# ProPrj_M0G3507__2025-04-02_2025-7-14_232.net
KiCad netlist of a schematic drawn in EasyEDA Pro
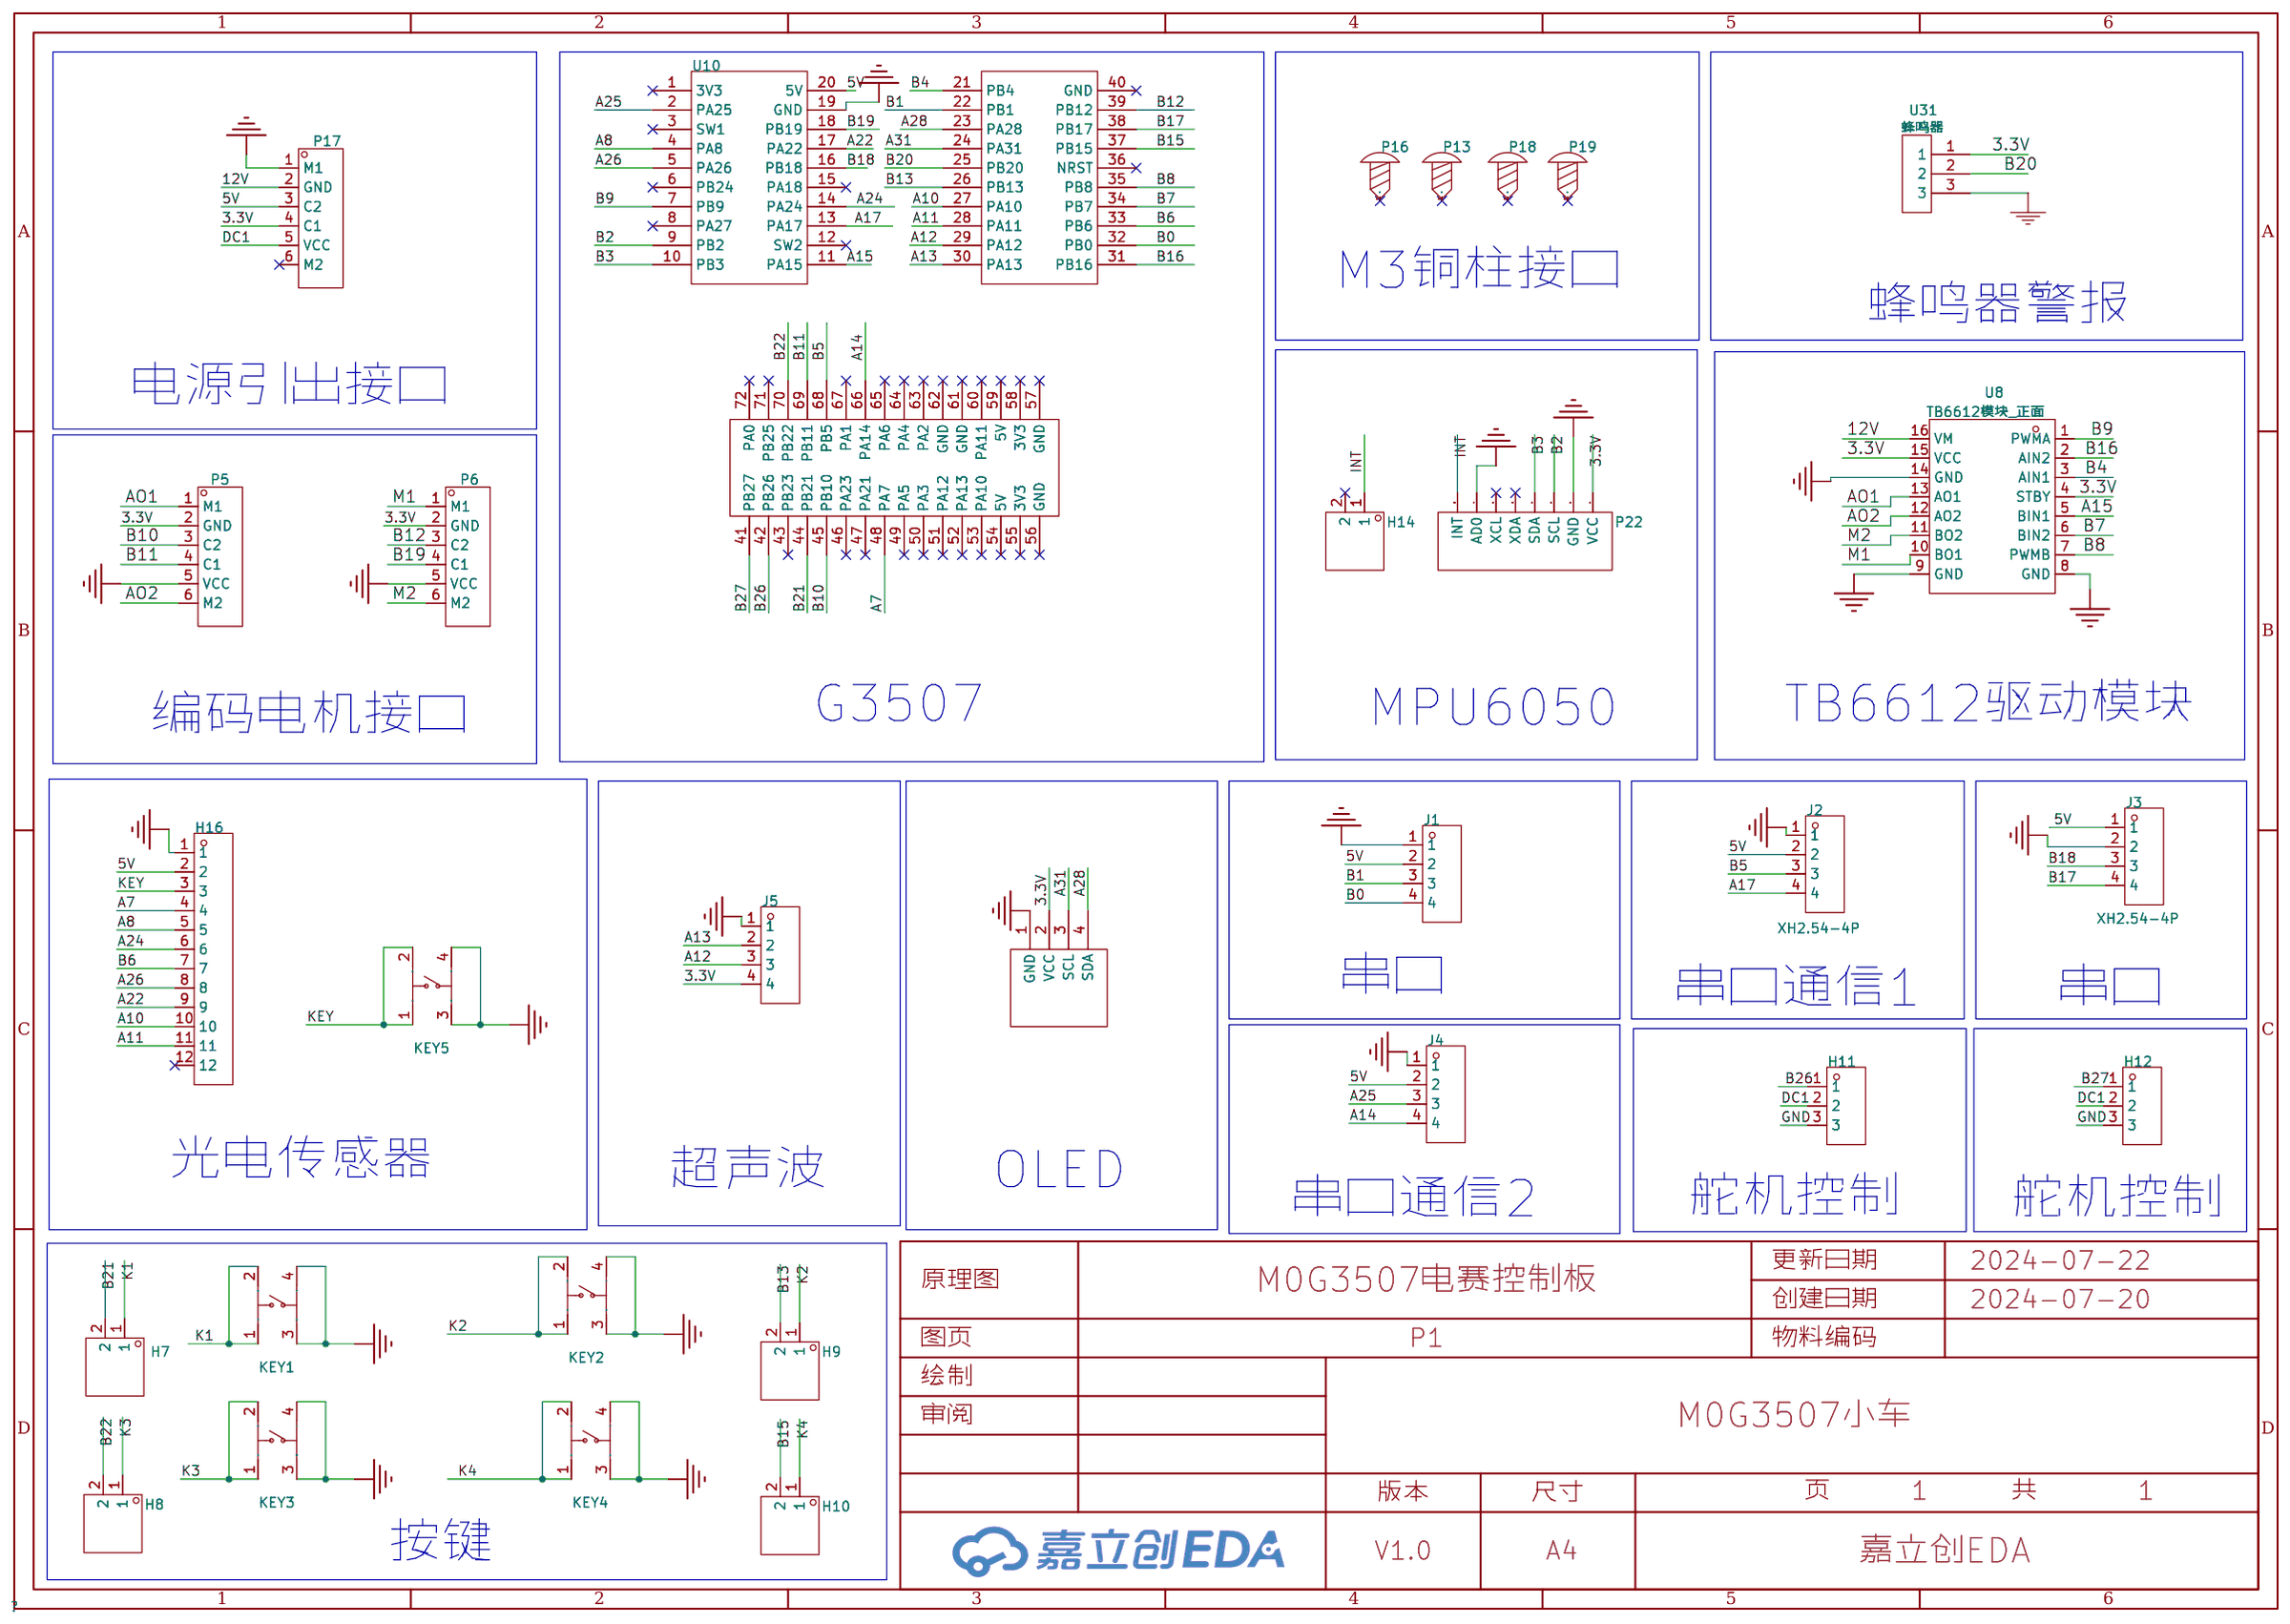
[diagram p0: schematic sheet]

(export (version "E")
  (design (tool "Eeschema 10.0.6"))
  (components
    (comp (ref "H7")
      (value "~")
      (footprint "easyedapro:HDR-TH_2P-P2.54-V-M-1")
      (fields (field (name "Manufacturer Part") "B-2100S02P-A110") (field (name "Manufacturer") "Ckmtw(灿科盟)"))
      (libsource (lib "easyedapro") (part "210S-1*2P L=11.6MMGold-plated black"))
    )
    (comp (ref "H8")
      (value "~")
      (footprint "easyedapro:HDR-TH_2P-P2.54-V-M-1")
      (fields (field (name "Manufacturer Part") "B-2100S02P-A110") (field (name "Manufacturer") "Ckmtw(灿科盟)"))
      (libsource (lib "easyedapro") (part "210S-1*2P L=11.6MMGold-plated black"))
    )
    (comp (ref "H9")
      (value "~")
      (footprint "easyedapro:HDR-TH_2P-P2.54-V-M-1")
      (fields (field (name "Manufacturer Part") "B-2100S02P-A110") (field (name "Manufacturer") "Ckmtw(灿科盟)"))
      (libsource (lib "easyedapro") (part "210S-1*2P L=11.6MMGold-plated black"))
    )
    (comp (ref "H10")
      (value "~")
      (footprint "easyedapro:HDR-TH_2P-P2.54-V-M-1")
      (fields (field (name "Manufacturer Part") "B-2100S02P-A110") (field (name "Manufacturer") "Ckmtw(灿科盟)"))
      (libsource (lib "easyedapro") (part "210S-1*2P L=11.6MMGold-plated black"))
    )
    (comp (ref "H11")
      (value "2.54-1*3P正弯针")
      (footprint "easyedapro:3P排针座")
      (fields (field (name "Manufacturer") "BOOMELE(博穆精密)"))
      (libsource (lib "easyedapro") (part "2.54-1*3P排针座"))
    )
    (comp (ref "H12")
      (value "2.54-1*3P正弯针")
      (footprint "easyedapro:3P排针座")
      (fields (field (name "Manufacturer") "BOOMELE(博穆精密)"))
      (libsource (lib "easyedapro") (part "2.54-1*3P排针座"))
    )
    (comp (ref "H14")
      (value "~")
      (footprint "easyedapro:HDR-TH_2P-P2.54-V-M-1")
      (fields (field (name "Manufacturer Part") "B-2100S02P-A110") (field (name "Manufacturer") "Ckmtw(灿科盟)"))
      (libsource (lib "easyedapro") (part "210S-1*2P L=11.6MMGold-plated black"))
    )
    (comp (ref "H16")
      (value "PZ254V-11-12P")
      (footprint "easyedapro:HDR-TH_12P-P2.54-V-M")
      (fields (field (name "Manufacturer") "XFCN(兴飞)"))
      (libsource (lib "easyedapro") (part "PZ254V-11-12P"))
    )
    (comp (ref "J1")
      (value "XH2.54-4P")
      (footprint "easyedapro:CONN-TH_4P-P2.50-XH2.54-4P")
      (libsource (lib "easyedapro") (part "XH2.54-4P"))
    )
    (comp (ref "J2")
      (value "XH2.54-4P")
      (footprint "easyedapro:CONN-TH_4P-P2.50-XH2.54-4P")
      (libsource (lib "easyedapro") (part "XH2.54-4P"))
    )
    (comp (ref "J3")
      (value "XH2.54-4P")
      (footprint "easyedapro:CONN-TH_4P-P2.50-XH2.54-4P")
      (libsource (lib "easyedapro") (part "XH2.54-4P"))
    )
    (comp (ref "J4")
      (value "XH2.54-4P")
      (footprint "easyedapro:CONN-TH_4P-P2.50-XH2.54-4P")
      (libsource (lib "easyedapro") (part "XH2.54-4P"))
    )
    (comp (ref "J5")
      (value "XH2.54-4P")
      (footprint "easyedapro:CONN-TH_4P-P2.50-XH2.54-4P")
      (libsource (lib "easyedapro") (part "XH2.54-4P"))
    )
    (comp (ref "KEY1")
      (value "TC-6610-9-260G")
      (footprint "easyedapro:SW-TH_4P-L5.0-W5.0-P4.50-LS6.5")
      (fields (field (name "Manufacturer") "HCTL(华灿天禄)"))
      (libsource (lib "easyedapro") (part "TC-6610-9-260G"))
    )
    (comp (ref "KEY2")
      (value "TC-6610-9-260G")
      (footprint "easyedapro:SW-TH_4P-L5.0-W5.0-P4.50-LS6.5")
      (fields (field (name "Manufacturer") "HCTL(华灿天禄)"))
      (libsource (lib "easyedapro") (part "TC-6610-9-260G"))
    )
    (comp (ref "KEY3")
      (value "TC-6610-9-260G")
      (footprint "easyedapro:SW-TH_4P-L5.0-W5.0-P4.50-LS6.5")
      (fields (field (name "Manufacturer") "HCTL(华灿天禄)"))
      (libsource (lib "easyedapro") (part "TC-6610-9-260G"))
    )
    (comp (ref "KEY4")
      (value "TC-6610-9-260G")
      (footprint "easyedapro:SW-TH_4P-L5.0-W5.0-P4.50-LS6.5")
      (fields (field (name "Manufacturer") "HCTL(华灿天禄)"))
      (libsource (lib "easyedapro") (part "TC-6610-9-260G"))
    )
    (comp (ref "KEY5")
      (value "TC-6610-9-260G")
      (footprint "easyedapro:SW-TH_4P-L5.0-W5.0-P4.50-LS6.5")
      (fields (field (name "Manufacturer") "HCTL(华灿天禄)"))
      (libsource (lib "easyedapro") (part "TC-6610-9-260G"))
    )
    (comp (ref "P5")
      (value "2.54pitch 6P")
      (footprint "easyedapro:footprint_2943")
      (fields (field (name "Manufacturer Part") "杜邦2.54-6A弯针") (field (name "Manufacturer") "BOOMELE(博穆精密)"))
      (libsource (lib "easyedapro") (part "2.54pitch 6P"))
    )
    (comp (ref "P6")
      (value "2.54pitch 6P")
      (footprint "easyedapro:footprint_2943")
      (fields (field (name "Manufacturer Part") "杜邦2.54-6A弯针") (field (name "Manufacturer") "BOOMELE(博穆精密)"))
      (libsource (lib "easyedapro") (part "2.54pitch 6P"))
    )
    (comp (ref "P13") (value "~") (footprint "easyedapro:M3螺丝") (libsource (lib "easyedapro") (part "螺丝孔")))
    (comp (ref "P16") (value "~") (footprint "easyedapro:M3螺丝") (libsource (lib "easyedapro") (part "螺丝孔")))
    (comp (ref "P17")
      (value "2.54pitch 6P")
      (footprint "easyedapro:footprint_2943")
      (fields (field (name "Manufacturer Part") "杜邦2.54-6A弯针") (field (name "Manufacturer") "BOOMELE(博穆精密)"))
      (libsource (lib "easyedapro") (part "2.54pitch 6P"))
    )
    (comp (ref "P18") (value "~") (footprint "easyedapro:M3螺丝") (libsource (lib "easyedapro") (part "螺丝孔")))
    (comp (ref "P19") (value "~") (footprint "easyedapro:M3螺丝") (libsource (lib "easyedapro") (part "螺丝孔")))
    (comp (ref "P22")
      (value "MPU6050模块")
      (footprint "easyedapro:MPU6050模块")
      (libsource (lib "easyedapro") (part "MPU6050模块"))
    )
    (comp (ref "U8")
      (value "TB6612模块_正面")
      (footprint "easyedapro:footprint_e1ec")
      (libsource (lib "easyedapro") (part "TB6612模块_正面"))
    )
    (comp (ref "U10")
      (value "~")
      (footprint "easyedapro:mspm0g3507")
      (libsource (lib "easyedapro") (part "mspm0g3507底座"))
    )
    (comp (ref "U31")
      (value "蜂鸣器")
      (footprint "easyedapro:footprint_f32e")
      (libsource (lib "easyedapro") (part "蜂鸣器"))
    )
    (comp (ref "U33")
      (value "0.96寸OLED")
      (footprint "easyedapro:0.96寸OLED")
      (libsource (lib "easyedapro") (part "0.96寸OLED"))
    )
  )
  (nets
    (net (code "1") (name "/3.3V") (class "Default")
      (node (ref "J5") (pin "4") (pinfunction "4_4") (pintype "input"))
      (node (ref "P17") (pin "4") (pinfunction "C1_4") (pintype "unspecified"))
      (node (ref "P22") (pin "1") (pinfunction "VCC_1") (pintype "input"))
      (node (ref "P5") (pin "2") (pinfunction "GND_2") (pintype "unspecified"))
      (node (ref "P6") (pin "2") (pinfunction "GND_2") (pintype "unspecified"))
      (node (ref "U31") (pin "1") (pinfunction "1_1") (pintype "unspecified"))
      (node (ref "U33") (pin "2") (pinfunction "VCC_2") (pintype "input"))
      (node (ref "U8") (pin "15") (pinfunction "VCC_15") (pintype "unspecified"))
      (node (ref "U8") (pin "4") (pinfunction "STBY_4") (pintype "unspecified"))
    )
    (net (code "2") (name "/5V") (class "Default")
      (node (ref "H16") (pin "2") (pinfunction "2_2") (pintype "unspecified"))
      (node (ref "J1") (pin "2") (pinfunction "2_2") (pintype "input"))
      (node (ref "J2") (pin "2") (pinfunction "2_2") (pintype "input"))
      (node (ref "J3") (pin "1") (pinfunction "1_1") (pintype "input"))
      (node (ref "J4") (pin "2") (pinfunction "2_2") (pintype "input"))
      (node (ref "P17") (pin "3") (pinfunction "C2_3") (pintype "unspecified"))
      (node (ref "U10") (pin "20") (pinfunction "5V_20") (pintype "input"))
    )
    (net (code "3") (name "/12V") (class "Default")
      (node (ref "P17") (pin "2") (pinfunction "GND_2") (pintype "unspecified"))
      (node (ref "U8") (pin "16") (pinfunction "VM_16") (pintype "unspecified"))
    )
    (net (code "4") (name "/A7") (class "Default")
      (node (ref "H16") (pin "4") (pinfunction "4_4") (pintype "unspecified"))
      (node (ref "U10") (pin "48") (pinfunction "PA7_48") (pintype "input"))
    )
    (net (code "5") (name "/A8") (class "Default")
      (node (ref "H16") (pin "5") (pinfunction "5_5") (pintype "unspecified"))
      (node (ref "U10") (pin "4") (pinfunction "PA8_4") (pintype "input"))
    )
    (net (code "6") (name "/A10") (class "Default")
      (node (ref "H16") (pin "10") (pinfunction "10_10") (pintype "unspecified"))
      (node (ref "U10") (pin "27") (pinfunction "PA10_27") (pintype "input"))
    )
    (net (code "7") (name "/A11") (class "Default")
      (node (ref "H16") (pin "11") (pinfunction "11_11") (pintype "unspecified"))
      (node (ref "U10") (pin "28") (pinfunction "PA11_28") (pintype "input"))
    )
    (net (code "8") (name "/A12") (class "Default")
      (node (ref "J5") (pin "3") (pinfunction "3_3") (pintype "input"))
      (node (ref "U10") (pin "29") (pinfunction "PA12_29") (pintype "input"))
    )
    (net (code "9") (name "/A13") (class "Default")
      (node (ref "J5") (pin "2") (pinfunction "2_2") (pintype "input"))
      (node (ref "U10") (pin "30") (pinfunction "PA13_30") (pintype "input"))
    )
    (net (code "10") (name "/A14") (class "Default")
      (node (ref "J4") (pin "4") (pinfunction "4_4") (pintype "input"))
      (node (ref "U10") (pin "66") (pinfunction "PA14_66") (pintype "input"))
    )
    (net (code "11") (name "/A15") (class "Default")
      (node (ref "U10") (pin "11") (pinfunction "PA15_11") (pintype "input"))
      (node (ref "U8") (pin "5") (pinfunction "BIN1_5") (pintype "unspecified"))
    )
    (net (code "12") (name "/A17") (class "Default")
      (node (ref "J2") (pin "4") (pinfunction "4_4") (pintype "input"))
      (node (ref "U10") (pin "13") (pinfunction "PA17_13") (pintype "input"))
    )
    (net (code "13") (name "/A22") (class "Default")
      (node (ref "H16") (pin "9") (pinfunction "9_9") (pintype "unspecified"))
      (node (ref "U10") (pin "17") (pinfunction "PA22_17") (pintype "input"))
    )
    (net (code "14") (name "/A24") (class "Default")
      (node (ref "H16") (pin "6") (pinfunction "6_6") (pintype "unspecified"))
      (node (ref "U10") (pin "14") (pinfunction "PA24_14") (pintype "input"))
    )
    (net (code "15") (name "/A25") (class "Default")
      (node (ref "J4") (pin "3") (pinfunction "3_3") (pintype "input"))
      (node (ref "U10") (pin "2") (pinfunction "PA25_2") (pintype "input"))
    )
    (net (code "16") (name "/A26") (class "Default")
      (node (ref "H16") (pin "8") (pinfunction "8_8") (pintype "unspecified"))
      (node (ref "U10") (pin "5") (pinfunction "PA26_5") (pintype "input"))
    )
    (net (code "17") (name "/A28") (class "Default")
      (node (ref "U10") (pin "23") (pinfunction "PA28_23") (pintype "input"))
      (node (ref "U33") (pin "4") (pinfunction "SDA_4") (pintype "input"))
    )
    (net (code "18") (name "/A31") (class "Default")
      (node (ref "U10") (pin "24") (pinfunction "PA31_24") (pintype "input"))
      (node (ref "U33") (pin "3") (pinfunction "SCL_3") (pintype "input"))
    )
    (net (code "19") (name "/AO1") (class "Default")
      (node (ref "P5") (pin "1") (pinfunction "M1_1") (pintype "unspecified"))
      (node (ref "U8") (pin "13") (pinfunction "AO1_13") (pintype "unspecified"))
    )
    (net (code "20") (name "/AO2") (class "Default")
      (node (ref "P5") (pin "6") (pinfunction "M2_6") (pintype "unspecified"))
      (node (ref "U8") (pin "12") (pinfunction "AO2_12") (pintype "unspecified"))
    )
    (net (code "21") (name "/B0") (class "Default")
      (node (ref "J1") (pin "4") (pinfunction "4_4") (pintype "input"))
      (node (ref "U10") (pin "32") (pinfunction "PB0_32") (pintype "input"))
    )
    (net (code "22") (name "/B1") (class "Default")
      (node (ref "J1") (pin "3") (pinfunction "3_3") (pintype "input"))
      (node (ref "U10") (pin "22") (pinfunction "PB1_22") (pintype "input"))
    )
    (net (code "23") (name "/B2") (class "Default")
      (node (ref "P22") (pin "3") (pinfunction "SCL_3") (pintype "input"))
      (node (ref "U10") (pin "9") (pinfunction "PB2_9") (pintype "input"))
    )
    (net (code "24") (name "/B3") (class "Default")
      (node (ref "P22") (pin "4") (pinfunction "SDA_4") (pintype "input"))
      (node (ref "U10") (pin "10") (pinfunction "PB3_10") (pintype "input"))
    )
    (net (code "25") (name "/B4") (class "Default")
      (node (ref "U10") (pin "21") (pinfunction "PB4_21") (pintype "input"))
      (node (ref "U8") (pin "3") (pinfunction "AIN1_3") (pintype "unspecified"))
    )
    (net (code "26") (name "/B5") (class "Default")
      (node (ref "J2") (pin "3") (pinfunction "3_3") (pintype "input"))
      (node (ref "U10") (pin "68") (pinfunction "PB5_68") (pintype "input"))
    )
    (net (code "27") (name "/B6") (class "Default")
      (node (ref "H16") (pin "7") (pinfunction "7_7") (pintype "unspecified"))
      (node (ref "U10") (pin "33") (pinfunction "PB6_33") (pintype "input"))
    )
    (net (code "28") (name "/B7") (class "Default")
      (node (ref "U10") (pin "34") (pinfunction "PB7_34") (pintype "input"))
      (node (ref "U8") (pin "6") (pinfunction "BIN2_6") (pintype "unspecified"))
    )
    (net (code "29") (name "/B8") (class "Default")
      (node (ref "U10") (pin "35") (pinfunction "PB8_35") (pintype "input"))
      (node (ref "U8") (pin "7") (pinfunction "PWMB_7") (pintype "unspecified"))
    )
    (net (code "30") (name "/B9") (class "Default")
      (node (ref "U10") (pin "7") (pinfunction "PB9_7") (pintype "input"))
      (node (ref "U8") (pin "1") (pinfunction "PWMA_1") (pintype "unspecified"))
    )
    (net (code "31") (name "/B10") (class "Default")
      (node (ref "P5") (pin "3") (pinfunction "C2_3") (pintype "unspecified"))
      (node (ref "U10") (pin "45") (pinfunction "PB10_45") (pintype "input"))
    )
    (net (code "32") (name "/B11") (class "Default")
      (node (ref "P5") (pin "4") (pinfunction "C1_4") (pintype "unspecified"))
      (node (ref "U10") (pin "69") (pinfunction "PB11_69") (pintype "input"))
    )
    (net (code "33") (name "/B12") (class "Default")
      (node (ref "P6") (pin "3") (pinfunction "C2_3") (pintype "unspecified"))
      (node (ref "U10") (pin "39") (pinfunction "PB12_39") (pintype "input"))
    )
    (net (code "34") (name "/B13") (class "Default")
      (node (ref "H9") (pin "2") (pinfunction "2_2") (pintype "input"))
      (node (ref "U10") (pin "26") (pinfunction "PB13_26") (pintype "input"))
    )
    (net (code "35") (name "/B15") (class "Default")
      (node (ref "H10") (pin "2") (pinfunction "2_2") (pintype "input"))
      (node (ref "U10") (pin "37") (pinfunction "PB15_37") (pintype "input"))
    )
    (net (code "36") (name "/B16") (class "Default")
      (node (ref "U10") (pin "31") (pinfunction "PB16_31") (pintype "input"))
      (node (ref "U8") (pin "2") (pinfunction "AIN2_2") (pintype "unspecified"))
    )
    (net (code "37") (name "/B17") (class "Default")
      (node (ref "J3") (pin "4") (pinfunction "4_4") (pintype "input"))
      (node (ref "U10") (pin "38") (pinfunction "PB17_38") (pintype "input"))
    )
    (net (code "38") (name "/B18") (class "Default")
      (node (ref "J3") (pin "3") (pinfunction "3_3") (pintype "input"))
      (node (ref "U10") (pin "16") (pinfunction "PB18_16") (pintype "input"))
    )
    (net (code "39") (name "/B19") (class "Default")
      (node (ref "P6") (pin "4") (pinfunction "C1_4") (pintype "unspecified"))
      (node (ref "U10") (pin "18") (pinfunction "PB19_18") (pintype "input"))
    )
    (net (code "40") (name "/B20") (class "Default")
      (node (ref "U10") (pin "25") (pinfunction "PB20_25") (pintype "input"))
      (node (ref "U31") (pin "2") (pinfunction "2_2") (pintype "unspecified"))
    )
    (net (code "41") (name "/B21") (class "Default")
      (node (ref "H7") (pin "2") (pinfunction "2_2") (pintype "input"))
      (node (ref "U10") (pin "44") (pinfunction "PB21_44") (pintype "input"))
    )
    (net (code "42") (name "/B22") (class "Default")
      (node (ref "H8") (pin "2") (pinfunction "2_2") (pintype "input"))
      (node (ref "U10") (pin "70") (pinfunction "PB22_70") (pintype "input"))
    )
    (net (code "43") (name "/B26") (class "Default")
      (node (ref "H11") (pin "1") (pinfunction "1_1") (pintype "input"))
      (node (ref "U10") (pin "42") (pinfunction "PB26_42") (pintype "input"))
    )
    (net (code "44") (name "/B27") (class "Default")
      (node (ref "H12") (pin "1") (pinfunction "1_1") (pintype "input"))
      (node (ref "U10") (pin "41") (pinfunction "PB27_41") (pintype "input"))
    )
    (net (code "45") (name "/DC1") (class "Default")
      (node (ref "H11") (pin "2") (pinfunction "2_2") (pintype "input"))
      (node (ref "H12") (pin "2") (pinfunction "2_2") (pintype "input"))
      (node (ref "P17") (pin "5") (pinfunction "VCC_5") (pintype "unspecified"))
    )
    (net (code "46") (name "/INT") (class "Default")
      (node (ref "H14") (pin "1") (pinfunction "1_1") (pintype "input"))
      (node (ref "P22") (pin "8") (pinfunction "INT_8") (pintype "input"))
    )
    (net (code "47") (name "/K1") (class "Default")
      (node (ref "H7") (pin "1") (pinfunction "1_1") (pintype "input"))
      (node (ref "KEY1") (pin "1") (pinfunction "1_1") (pintype "input"))
      (node (ref "KEY1") (pin "2") (pinfunction "2_2") (pintype "input"))
    )
    (net (code "48") (name "/K2") (class "Default")
      (node (ref "H9") (pin "1") (pinfunction "1_1") (pintype "input"))
      (node (ref "KEY2") (pin "1") (pinfunction "1_1") (pintype "input"))
      (node (ref "KEY2") (pin "2") (pinfunction "2_2") (pintype "input"))
    )
    (net (code "49") (name "/K3") (class "Default")
      (node (ref "H8") (pin "1") (pinfunction "1_1") (pintype "input"))
      (node (ref "KEY3") (pin "1") (pinfunction "1_1") (pintype "input"))
      (node (ref "KEY3") (pin "2") (pinfunction "2_2") (pintype "input"))
    )
    (net (code "50") (name "/K4") (class "Default")
      (node (ref "H10") (pin "1") (pinfunction "1_1") (pintype "input"))
      (node (ref "KEY4") (pin "1") (pinfunction "1_1") (pintype "input"))
      (node (ref "KEY4") (pin "2") (pinfunction "2_2") (pintype "input"))
    )
    (net (code "51") (name "/KEY") (class "Default")
      (node (ref "H16") (pin "3") (pinfunction "3_3") (pintype "unspecified"))
      (node (ref "KEY5") (pin "1") (pinfunction "1_1") (pintype "input"))
      (node (ref "KEY5") (pin "2") (pinfunction "2_2") (pintype "input"))
    )
    (net (code "52") (name "/M1") (class "Default")
      (node (ref "P6") (pin "1") (pinfunction "M1_1") (pintype "unspecified"))
      (node (ref "U8") (pin "10") (pinfunction "BO1_10") (pintype "unspecified"))
    )
    (net (code "53") (name "/M2") (class "Default")
      (node (ref "P6") (pin "6") (pinfunction "M2_6") (pintype "unspecified"))
      (node (ref "U8") (pin "11") (pinfunction "BO2_11") (pintype "unspecified"))
    )
    (net (code "54") (name "GND") (class "Default")
      (node (ref "H11") (pin "3") (pinfunction "3_3") (pintype "input"))
      (node (ref "H12") (pin "3") (pinfunction "3_3") (pintype "input"))
      (node (ref "H16") (pin "1") (pinfunction "1_1") (pintype "unspecified"))
      (node (ref "J1") (pin "1") (pinfunction "1_1") (pintype "input"))
      (node (ref "J2") (pin "1") (pinfunction "1_1") (pintype "input"))
      (node (ref "J3") (pin "2") (pinfunction "2_2") (pintype "input"))
      (node (ref "J4") (pin "1") (pinfunction "1_1") (pintype "input"))
      (node (ref "J5") (pin "1") (pinfunction "1_1") (pintype "input"))
      (node (ref "KEY1") (pin "3") (pinfunction "3_3") (pintype "input"))
      (node (ref "KEY1") (pin "4") (pinfunction "4_4") (pintype "input"))
      (node (ref "KEY2") (pin "3") (pinfunction "3_3") (pintype "input"))
      (node (ref "KEY2") (pin "4") (pinfunction "4_4") (pintype "input"))
      (node (ref "KEY3") (pin "3") (pinfunction "3_3") (pintype "input"))
      (node (ref "KEY3") (pin "4") (pinfunction "4_4") (pintype "input"))
      (node (ref "KEY4") (pin "3") (pinfunction "3_3") (pintype "input"))
      (node (ref "KEY4") (pin "4") (pinfunction "4_4") (pintype "input"))
      (node (ref "KEY5") (pin "3") (pinfunction "3_3") (pintype "input"))
      (node (ref "KEY5") (pin "4") (pinfunction "4_4") (pintype "input"))
      (node (ref "P17") (pin "1") (pinfunction "M1_1") (pintype "unspecified"))
      (node (ref "P22") (pin "2") (pinfunction "GND_2") (pintype "input"))
      (node (ref "P22") (pin "7") (pinfunction "AD0_7") (pintype "input"))
      (node (ref "P5") (pin "5") (pinfunction "VCC_5") (pintype "unspecified"))
      (node (ref "P6") (pin "5") (pinfunction "VCC_5") (pintype "unspecified"))
      (node (ref "U10") (pin "19") (pinfunction "GND_19") (pintype "input"))
      (node (ref "U31") (pin "3") (pinfunction "3_3") (pintype "unspecified"))
      (node (ref "U33") (pin "1") (pinfunction "GND_1") (pintype "input"))
      (node (ref "U8") (pin "14") (pinfunction "GND_14") (pintype "unspecified"))
      (node (ref "U8") (pin "8") (pinfunction "GND_8") (pintype "unspecified"))
      (node (ref "U8") (pin "9") (pinfunction "GND_9") (pintype "unspecified"))
    )
    (net (code "55") (name "unconnected-(H14-Pad2)") (class "Default")
      (node (ref "H14") (pin "2") (pinfunction "2_2") (pintype "input+no_connect"))
    )
    (net (code "56") (name "unconnected-(H16-Pad12)") (class "Default")
      (node (ref "H16") (pin "12") (pinfunction "12_12") (pintype "unspecified+no_connect"))
    )
    (net (code "57") (name "unconnected-(P13-Pad1)") (class "Default")
      (node (ref "P13") (pin "1") (pinfunction "1_1") (pintype "input+no_connect"))
    )
    (net (code "58") (name "unconnected-(P16-Pad1)") (class "Default")
      (node (ref "P16") (pin "1") (pinfunction "1_1") (pintype "input+no_connect"))
    )
    (net (code "59") (name "unconnected-(P17-M2-Pad6)") (class "Default")
      (node (ref "P17") (pin "6") (pinfunction "M2_6") (pintype "unspecified+no_connect"))
    )
    (net (code "60") (name "unconnected-(P18-Pad1)") (class "Default")
      (node (ref "P18") (pin "1") (pinfunction "1_1") (pintype "input+no_connect"))
    )
    (net (code "61") (name "unconnected-(P19-Pad1)") (class "Default")
      (node (ref "P19") (pin "1") (pinfunction "1_1") (pintype "input+no_connect"))
    )
    (net (code "62") (name "unconnected-(P22-XCL-Pad6)") (class "Default")
      (node (ref "P22") (pin "6") (pinfunction "XCL_6") (pintype "input+no_connect"))
    )
    (net (code "63") (name "unconnected-(P22-XDA-Pad5)") (class "Default")
      (node (ref "P22") (pin "5") (pinfunction "XDA_5") (pintype "input+no_connect"))
    )
    (net (code "64") (name "unconnected-(U10-3V3-Pad1)") (class "Default")
      (node (ref "U10") (pin "1") (pinfunction "3V3_1") (pintype "input+no_connect"))
    )
    (net (code "65") (name "unconnected-(U10-3V3-Pad55)") (class "Default")
      (node (ref "U10") (pin "55") (pinfunction "3V3_55") (pintype "input+no_connect"))
    )
    (net (code "66") (name "unconnected-(U10-3V3-Pad58)") (class "Default")
      (node (ref "U10") (pin "58") (pinfunction "3V3_58") (pintype "input+no_connect"))
    )
    (net (code "67") (name "unconnected-(U10-5V-Pad54)") (class "Default")
      (node (ref "U10") (pin "54") (pinfunction "5V_54") (pintype "input+no_connect"))
    )
    (net (code "68") (name "unconnected-(U10-5V-Pad59)") (class "Default")
      (node (ref "U10") (pin "59") (pinfunction "5V_59") (pintype "input+no_connect"))
    )
    (net (code "69") (name "unconnected-(U10-GND-Pad40)") (class "Default")
      (node (ref "U10") (pin "40") (pinfunction "GND_40") (pintype "input+no_connect"))
    )
    (net (code "70") (name "unconnected-(U10-GND-Pad56)") (class "Default")
      (node (ref "U10") (pin "56") (pinfunction "GND_56") (pintype "input+no_connect"))
    )
    (net (code "71") (name "unconnected-(U10-GND-Pad57)") (class "Default")
      (node (ref "U10") (pin "57") (pinfunction "GND_57") (pintype "input+no_connect"))
    )
    (net (code "72") (name "unconnected-(U10-GND-Pad61)") (class "Default")
      (node (ref "U10") (pin "61") (pinfunction "GND_61") (pintype "input+no_connect"))
    )
    (net (code "73") (name "unconnected-(U10-GND-Pad62)") (class "Default")
      (node (ref "U10") (pin "62") (pinfunction "GND_62") (pintype "input+no_connect"))
    )
    (net (code "74") (name "unconnected-(U10-NRST-Pad36)") (class "Default")
      (node (ref "U10") (pin "36") (pinfunction "NRST_36") (pintype "input+no_connect"))
    )
    (net (code "75") (name "unconnected-(U10-PA0-Pad72)") (class "Default")
      (node (ref "U10") (pin "72") (pinfunction "PA0_72") (pintype "input+no_connect"))
    )
    (net (code "76") (name "unconnected-(U10-PA1-Pad67)") (class "Default")
      (node (ref "U10") (pin "67") (pinfunction "PA1_67") (pintype "input+no_connect"))
    )
    (net (code "77") (name "unconnected-(U10-PA2-Pad63)") (class "Default")
      (node (ref "U10") (pin "63") (pinfunction "PA2_63") (pintype "input+no_connect"))
    )
    (net (code "78") (name "unconnected-(U10-PA3-Pad50)") (class "Default")
      (node (ref "U10") (pin "50") (pinfunction "PA3_50") (pintype "input+no_connect"))
    )
    (net (code "79") (name "unconnected-(U10-PA4-Pad64)") (class "Default")
      (node (ref "U10") (pin "64") (pinfunction "PA4_64") (pintype "input+no_connect"))
    )
    (net (code "80") (name "unconnected-(U10-PA5-Pad49)") (class "Default")
      (node (ref "U10") (pin "49") (pinfunction "PA5_49") (pintype "input+no_connect"))
    )
    (net (code "81") (name "unconnected-(U10-PA6-Pad65)") (class "Default")
      (node (ref "U10") (pin "65") (pinfunction "PA6_65") (pintype "input+no_connect"))
    )
    (net (code "82") (name "unconnected-(U10-PA10-Pad53)") (class "Default")
      (node (ref "U10") (pin "53") (pinfunction "PA10_53") (pintype "input+no_connect"))
    )
    (net (code "83") (name "unconnected-(U10-PA11-Pad60)") (class "Default")
      (node (ref "U10") (pin "60") (pinfunction "PA11_60") (pintype "input+no_connect"))
    )
    (net (code "84") (name "unconnected-(U10-PA12-Pad51)") (class "Default")
      (node (ref "U10") (pin "51") (pinfunction "PA12_51") (pintype "input+no_connect"))
    )
    (net (code "85") (name "unconnected-(U10-PA13-Pad52)") (class "Default")
      (node (ref "U10") (pin "52") (pinfunction "PA13_52") (pintype "input+no_connect"))
    )
    (net (code "86") (name "unconnected-(U10-PA18-Pad15)") (class "Default")
      (node (ref "U10") (pin "15") (pinfunction "PA18_15") (pintype "input+no_connect"))
    )
    (net (code "87") (name "unconnected-(U10-PA21-Pad47)") (class "Default")
      (node (ref "U10") (pin "47") (pinfunction "PA21_47") (pintype "input+no_connect"))
    )
    (net (code "88") (name "unconnected-(U10-PA23-Pad46)") (class "Default")
      (node (ref "U10") (pin "46") (pinfunction "PA23_46") (pintype "input+no_connect"))
    )
    (net (code "89") (name "unconnected-(U10-PA27-Pad8)") (class "Default")
      (node (ref "U10") (pin "8") (pinfunction "PA27_8") (pintype "input+no_connect"))
    )
    (net (code "90") (name "unconnected-(U10-PB23-Pad43)") (class "Default")
      (node (ref "U10") (pin "43") (pinfunction "PB23_43") (pintype "input+no_connect"))
    )
    (net (code "91") (name "unconnected-(U10-PB24-Pad6)") (class "Default")
      (node (ref "U10") (pin "6") (pinfunction "PB24_6") (pintype "input+no_connect"))
    )
    (net (code "92") (name "unconnected-(U10-PB25-Pad71)") (class "Default")
      (node (ref "U10") (pin "71") (pinfunction "PB25_71") (pintype "input+no_connect"))
    )
    (net (code "93") (name "unconnected-(U10-SW1-Pad3)") (class "Default")
      (node (ref "U10") (pin "3") (pinfunction "SW1_3") (pintype "input+no_connect"))
    )
    (net (code "94") (name "unconnected-(U10-SW2-Pad12)") (class "Default")
      (node (ref "U10") (pin "12") (pinfunction "SW2_12") (pintype "input+no_connect"))
    )
  )
)
